# v1-mouse-has-canduino.net
KiCad netlist of a schematic drawn in EAGLE
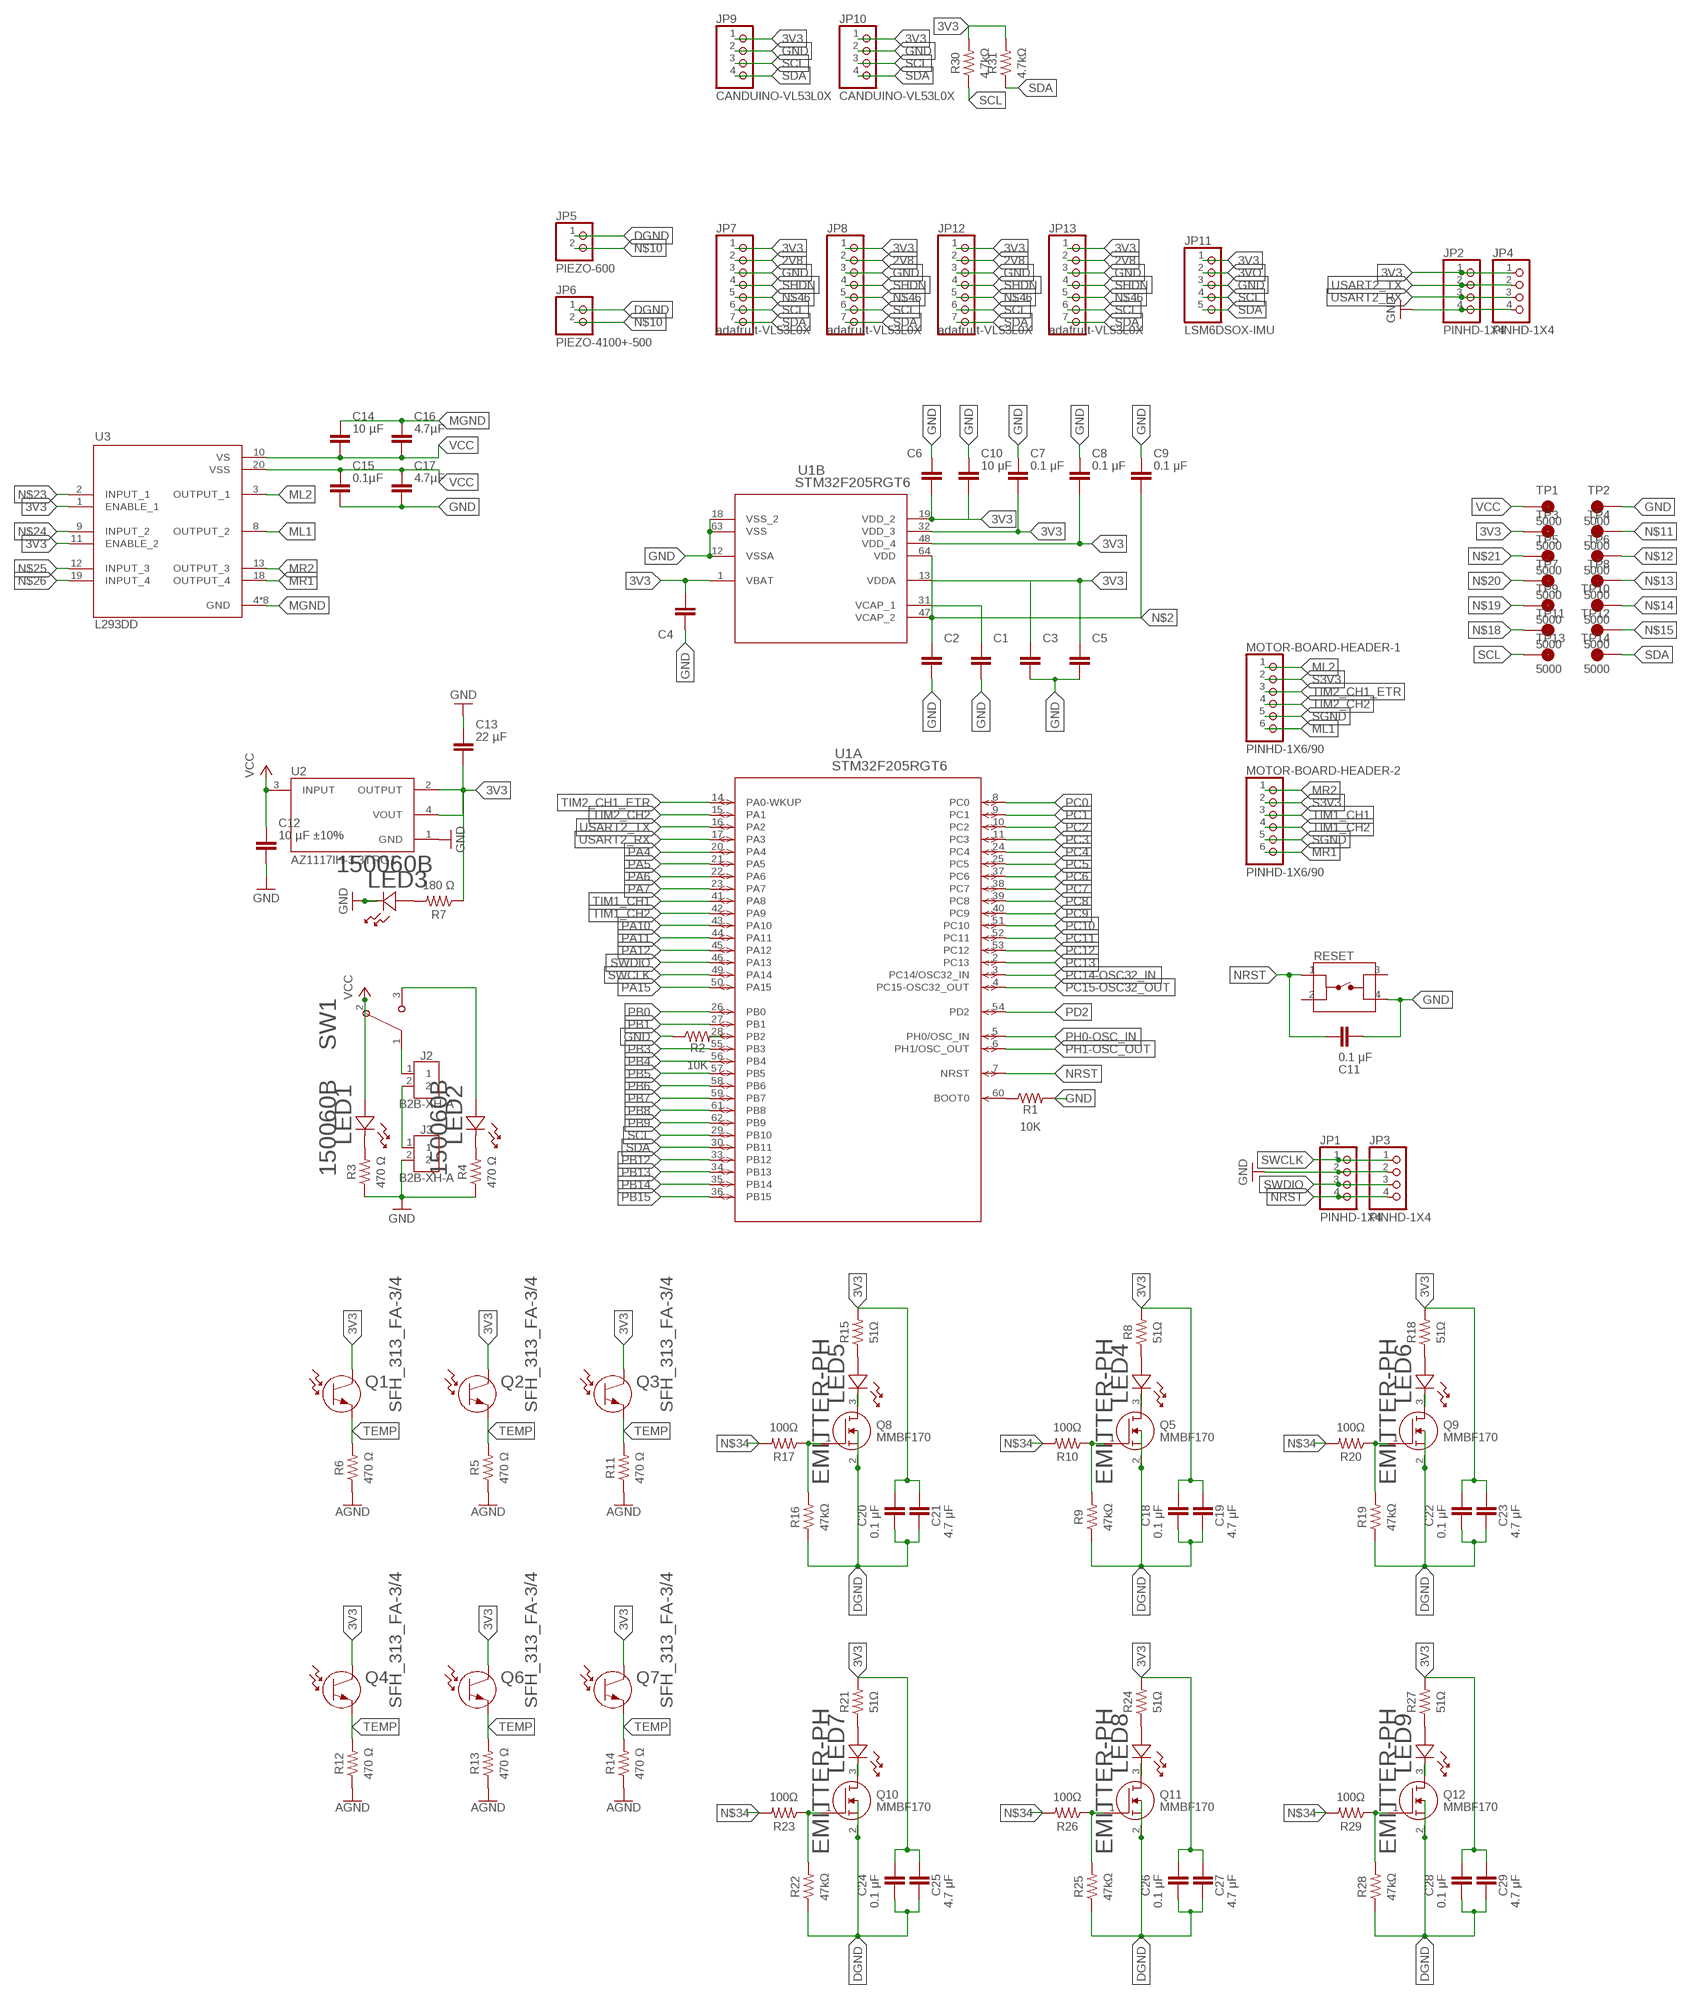
[diagram p0: schematic, sheet 1]

(export (version "E")
  (design (tool "Eeschema 10.0.6"))
  (components
    (comp (ref "C1")
      (value "2.2 μF")
      (footprint "eagle-import:CAPC1608X85")
      (libsource (lib "eagle-import") (part "CCHIP-0603(1608-METRIC)_"))
    )
    (comp (ref "C2")
      (value "2.2 μF")
      (footprint "eagle-import:CAPC1608X85")
      (libsource (lib "eagle-import") (part "CCHIP-0603(1608-METRIC)_"))
    )
    (comp (ref "C3")
      (value "0.1 μF")
      (footprint "eagle-import:CAPC1608X85")
      (libsource (lib "eagle-import") (part "CCHIP-0603(1608-METRIC)_"))
    )
    (comp (ref "C4")
      (value "0.1 μF")
      (footprint "eagle-import:CAPC1608X85")
      (libsource (lib "eagle-import") (part "CCHIP-0603(1608-METRIC)_"))
    )
    (comp (ref "C5")
      (value "1 μF")
      (footprint "eagle-import:CAPC1608X85")
      (libsource (lib "eagle-import") (part "CCHIP-0603(1608-METRIC)_"))
    )
    (comp (ref "C6")
      (value "0.1 μF")
      (footprint "eagle-import:CAPC1608X85")
      (libsource (lib "eagle-import") (part "CCHIP-0603(1608-METRIC)_"))
    )
    (comp (ref "C7")
      (value "0.1 μF")
      (footprint "eagle-import:CAPC1608X85")
      (libsource (lib "eagle-import") (part "Capacitor2_CCHIP-0603(1608-METRIC)_"))
    )
    (comp (ref "C8")
      (value "0.1 μF")
      (footprint "eagle-import:CAPC1608X85")
      (libsource (lib "eagle-import") (part "Capacitor2_CCHIP-0603(1608-METRIC)_"))
    )
    (comp (ref "C9")
      (value "0.1 μF")
      (footprint "eagle-import:CAPC1608X85")
      (libsource (lib "eagle-import") (part "Capacitor2_CCHIP-0603(1608-METRIC)_"))
    )
    (comp (ref "C10")
      (value "10 μF")
      (footprint "eagle-import:CAPC1608X85")
      (libsource (lib "eagle-import") (part "Capacitor2_CCHIP-0603(1608-METRIC)_"))
    )
    (comp (ref "C11")
      (value "0.1 μF")
      (footprint "eagle-import:CAPC1608X85")
      (libsource (lib "eagle-import") (part "Capacitor2_CCHIP-0603(1608-METRIC)_"))
    )
    (comp (ref "C12")
      (value "10 µF ±10%")
      (footprint "eagle-import:CAPC1608X85")
      (libsource (lib "eagle-import") (part "CCHIP-0603(1608-METRIC)_"))
    )
    (comp (ref "C13")
      (value "22 µF")
      (footprint "eagle-import:CAPC1608X85")
      (libsource (lib "eagle-import") (part "CCHIP-0603(1608-METRIC)_"))
    )
    (comp (ref "C14")
      (value "10 µF")
      (footprint "eagle-import:CAPC1608X85")
      (libsource (lib "eagle-import") (part "CCHIP-0603(1608-METRIC)_"))
    )
    (comp (ref "C15")
      (value "0.1µF")
      (footprint "eagle-import:CAPC1608X85")
      (libsource (lib "eagle-import") (part "CCHIP-0603(1608-METRIC)_"))
    )
    (comp (ref "C16")
      (value "4.7µF")
      (footprint "eagle-import:CAPC1608X85")
      (libsource (lib "eagle-import") (part "CCHIP-0603(1608-METRIC)_"))
    )
    (comp (ref "C17")
      (value "4.7µF")
      (footprint "eagle-import:CAPC1608X85")
      (libsource (lib "eagle-import") (part "CCHIP-0603(1608-METRIC)_"))
    )
    (comp (ref "C18")
      (value "0.1 μF")
      (footprint "eagle-import:CAPC1608X85")
      (libsource (lib "eagle-import") (part "Capacitor2_CCHIP-0603(1608-METRIC)_"))
    )
    (comp (ref "C19")
      (value "4.7 μF")
      (footprint "eagle-import:CAPC1608X85")
      (libsource (lib "eagle-import") (part "Capacitor2_CCHIP-0603(1608-METRIC)_"))
    )
    (comp (ref "C20")
      (value "0.1 μF")
      (footprint "eagle-import:CAPC1608X85")
      (libsource (lib "eagle-import") (part "Capacitor2_CCHIP-0603(1608-METRIC)_"))
    )
    (comp (ref "C21")
      (value "4.7 μF")
      (footprint "eagle-import:CAPC1608X85")
      (libsource (lib "eagle-import") (part "Capacitor2_CCHIP-0603(1608-METRIC)_"))
    )
    (comp (ref "C22")
      (value "0.1 μF")
      (footprint "eagle-import:CAPC1608X85")
      (libsource (lib "eagle-import") (part "Capacitor2_CCHIP-0603(1608-METRIC)_"))
    )
    (comp (ref "C23")
      (value "4.7 μF")
      (footprint "eagle-import:CAPC1608X85")
      (libsource (lib "eagle-import") (part "Capacitor2_CCHIP-0603(1608-METRIC)_"))
    )
    (comp (ref "C24")
      (value "0.1 μF")
      (footprint "eagle-import:CAPC1608X85")
      (libsource (lib "eagle-import") (part "Capacitor2_CCHIP-0603(1608-METRIC)_"))
    )
    (comp (ref "C25")
      (value "4.7 μF")
      (footprint "eagle-import:CAPC1608X85")
      (libsource (lib "eagle-import") (part "Capacitor2_CCHIP-0603(1608-METRIC)_"))
    )
    (comp (ref "C26")
      (value "0.1 μF")
      (footprint "eagle-import:CAPC1608X85")
      (libsource (lib "eagle-import") (part "Capacitor2_CCHIP-0603(1608-METRIC)_"))
    )
    (comp (ref "C27")
      (value "4.7 μF")
      (footprint "eagle-import:CAPC1608X85")
      (libsource (lib "eagle-import") (part "Capacitor2_CCHIP-0603(1608-METRIC)_"))
    )
    (comp (ref "C28")
      (value "0.1 μF")
      (footprint "eagle-import:CAPC1608X85")
      (libsource (lib "eagle-import") (part "Capacitor2_CCHIP-0603(1608-METRIC)_"))
    )
    (comp (ref "C29")
      (value "4.7 μF")
      (footprint "eagle-import:CAPC1608X85")
      (libsource (lib "eagle-import") (part "Capacitor2_CCHIP-0603(1608-METRIC)_"))
    )
    (comp (ref "J2")
      (value "B2B-XH-A")
      (footprint "eagle-import:B2B-XH-A")
      (fields
        (field (name "MANUFACTURER") "JST Sales America Inc. ")
        (field (name "MPN") "B2B-XH-A(LF)(SN) ")
      )
      (libsource (lib "eagle-import") (part "B2B-XH-A"))
    )
    (comp (ref "J3")
      (value "B2B-XH-A")
      (footprint "eagle-import:B2B-XH-A")
      (fields
        (field (name "MANUFACTURER") "JST Sales America Inc. ")
        (field (name "MPN") "B2B-XH-A(LF)(SN) ")
      )
      (libsource (lib "eagle-import") (part "B2B-XH-A"))
    )
    (comp (ref "JP1")
      (value "PINHD-1X4")
      (footprint "eagle-import:1X04")
      (fields (field (name "MANUFACTURER") "Generic"))
      (libsource (lib "eagle-import") (part "PINHD-1X4"))
    )
    (comp (ref "JP2")
      (value "PINHD-1X4")
      (footprint "eagle-import:1X04")
      (fields (field (name "MANUFACTURER") "Generic"))
      (libsource (lib "eagle-import") (part "PINHD-1X4"))
    )
    (comp (ref "JP3")
      (value "PINHD-1X4")
      (footprint "eagle-import:1X04")
      (fields (field (name "MANUFACTURER") "Generic"))
      (libsource (lib "eagle-import") (part "PINHD-1X4"))
    )
    (comp (ref "JP4")
      (value "PINHD-1X4")
      (footprint "eagle-import:1X04")
      (fields (field (name "MANUFACTURER") "Generic"))
      (libsource (lib "eagle-import") (part "PINHD-1X4"))
    )
    (comp (ref "JP5")
      (value "PIEZO-600")
      (footprint "eagle-import:1X02_90")
      (fields (field (name "MANUFACTURER") "Generic"))
      (libsource (lib "eagle-import") (part "PINHD-1X2/90"))
    )
    (comp (ref "JP6")
      (value "PIEZO-4100+-500")
      (footprint "eagle-import:1X02_90")
      (fields (field (name "MANUFACTURER") "Generic"))
      (libsource (lib "eagle-import") (part "PINHD-1X2/90"))
    )
    (comp (ref "JP7")
      (value "adafruit-VL53L0X")
      (footprint "eagle-import:1X07_90")
      (fields (field (name "MANUFACTURER") "Generic"))
      (libsource (lib "eagle-import") (part "PINHD-1X7/90"))
    )
    (comp (ref "JP8")
      (value "adafruit-VL53L0X")
      (footprint "eagle-import:1X07_90")
      (fields (field (name "MANUFACTURER") "Generic"))
      (libsource (lib "eagle-import") (part "PINHD-1X7/90"))
    )
    (comp (ref "JP9")
      (value "CANDUINO-VL53L0X")
      (footprint "eagle-import:1X04_90")
      (fields (field (name "MANUFACTURER") "Generic"))
      (libsource (lib "eagle-import") (part "PINHD-1X4/90"))
    )
    (comp (ref "JP10")
      (value "CANDUINO-VL53L0X")
      (footprint "eagle-import:1X04_90")
      (fields (field (name "MANUFACTURER") "Generic"))
      (libsource (lib "eagle-import") (part "PINHD-1X4/90"))
    )
    (comp (ref "JP11")
      (value "LSM6DSOX-IMU")
      (footprint "eagle-import:1_05X2MM")
      (fields (field (name "MANUFACTURER") "Generic"))
      (libsource (lib "eagle-import") (part "PINHD-1X55X2MM"))
    )
    (comp (ref "JP12")
      (value "adafruit-VL53L0X")
      (footprint "eagle-import:1X07_90")
      (fields (field (name "MANUFACTURER") "Generic"))
      (libsource (lib "eagle-import") (part "PINHD-1X7/90"))
    )
    (comp (ref "JP13")
      (value "adafruit-VL53L0X")
      (footprint "eagle-import:1X07_90")
      (fields (field (name "MANUFACTURER") "Generic"))
      (libsource (lib "eagle-import") (part "PINHD-1X7/90"))
    )
    (comp (ref "LED1")
      (value "150060B")
      (footprint "eagle-import:LED_150060B_WRE-L")
      (fields
        (field (name "MANUFACTURER_PART_NUMBER") "150060VS55040")
        (field (name "COPYRIGHT") "Copyright (C) 2024 Ultra Librarian. All rights reserved.")
      )
      (libsource (lib "eagle-import") (part "150060VS55040LED_150060B_WRE-L"))
    )
    (comp (ref "LED2")
      (value "150060B")
      (footprint "eagle-import:LED_150060B_WRE-L")
      (fields
        (field (name "MANUFACTURER_PART_NUMBER") "150060VS55040")
        (field (name "COPYRIGHT") "Copyright (C) 2024 Ultra Librarian. All rights reserved.")
      )
      (libsource (lib "eagle-import") (part "150060VS55040LED_150060B_WRE-L"))
    )
    (comp (ref "LED3")
      (value "150060B")
      (footprint "eagle-import:LED_150060B_WRE-L")
      (fields
        (field (name "MANUFACTURER_PART_NUMBER") "150060VS55040")
        (field (name "COPYRIGHT") "Copyright (C) 2024 Ultra Librarian. All rights reserved.")
      )
      (libsource (lib "eagle-import") (part "150060VS55040LED_150060B_WRE-L"))
    )
    (comp (ref "LED4")
      (value "EMITTER-PH")
      (footprint "eagle-import:LED_B1911PG--20D000514U1930_01")
      (fields
        (field (name "MANUFACTURER_PART_NUMBER") "B1911PG--20D000514U1930")
        (field (name "COPYRIGHT") "Copyright (C) 2024 Ultra Librarian. All rights reserved.")
      )
      (libsource (lib "eagle-import") (part "B1911PG--20D000514U1930LED_B1911PG--20D000514U1930_01"))
    )
    (comp (ref "LED5")
      (value "EMITTER-PH")
      (footprint "eagle-import:LED_B1911PG--20D000514U1930_01")
      (fields
        (field (name "MANUFACTURER_PART_NUMBER") "B1911PG--20D000514U1930")
        (field (name "COPYRIGHT") "Copyright (C) 2024 Ultra Librarian. All rights reserved.")
      )
      (libsource (lib "eagle-import") (part "B1911PG--20D000514U1930LED_B1911PG--20D000514U1930_01"))
    )
    (comp (ref "LED6")
      (value "EMITTER-PH")
      (footprint "eagle-import:LED_B1911PG--20D000514U1930_01")
      (fields
        (field (name "MANUFACTURER_PART_NUMBER") "B1911PG--20D000514U1930")
        (field (name "COPYRIGHT") "Copyright (C) 2024 Ultra Librarian. All rights reserved.")
      )
      (libsource (lib "eagle-import") (part "B1911PG--20D000514U1930LED_B1911PG--20D000514U1930_01"))
    )
    (comp (ref "LED7")
      (value "EMITTER-PH")
      (footprint "eagle-import:LED_B1911PG--20D000514U1930_01")
      (fields
        (field (name "MANUFACTURER_PART_NUMBER") "B1911PG--20D000514U1930")
        (field (name "COPYRIGHT") "Copyright (C) 2024 Ultra Librarian. All rights reserved.")
      )
      (libsource (lib "eagle-import") (part "B1911PG--20D000514U1930LED_B1911PG--20D000514U1930_01"))
    )
    (comp (ref "LED8")
      (value "EMITTER-PH")
      (footprint "eagle-import:LED_B1911PG--20D000514U1930_01")
      (fields
        (field (name "MANUFACTURER_PART_NUMBER") "B1911PG--20D000514U1930")
        (field (name "COPYRIGHT") "Copyright (C) 2024 Ultra Librarian. All rights reserved.")
      )
      (libsource (lib "eagle-import") (part "B1911PG--20D000514U1930LED_B1911PG--20D000514U1930_01"))
    )
    (comp (ref "LED9")
      (value "EMITTER-PH")
      (footprint "eagle-import:LED_B1911PG--20D000514U1930_01")
      (fields
        (field (name "MANUFACTURER_PART_NUMBER") "B1911PG--20D000514U1930")
        (field (name "COPYRIGHT") "Copyright (C) 2024 Ultra Librarian. All rights reserved.")
      )
      (libsource (lib "eagle-import") (part "B1911PG--20D000514U1930LED_B1911PG--20D000514U1930_01"))
    )
    (comp (ref "MOTOR-BOARD-HEADER-1")
      (value "PINHD-1X6/90")
      (footprint "eagle-import:1X06_90")
      (fields (field (name "MANUFACTURER") "Generic"))
      (libsource (lib "eagle-import") (part "PINHD-1X6/90"))
    )
    (comp (ref "MOTOR-BOARD-HEADER-2")
      (value "PINHD-1X6/90")
      (footprint "eagle-import:1X06_90")
      (fields (field (name "MANUFACTURER") "Generic"))
      (libsource (lib "eagle-import") (part "PINHD-1X6/90"))
    )
    (comp (ref "Q1")
      (value "SFH_313_FA-3/4")
      (footprint "eagle-import:SFH_313_FA-3_4_OSR")
      (fields
        (field (name "MANUFACTURER_PART_NUMBER") "SFH 313 FA-3/4")
        (field (name "COPYRIGHT") "Copyright (C) 2024 Ultra Librarian. All rights reserved.")
      )
      (libsource (lib "eagle-import") (part "SFH_313_FA-3/4SFH_313_FA-3/4_OSR"))
    )
    (comp (ref "Q2")
      (value "SFH_313_FA-3/4")
      (footprint "eagle-import:SFH_313_FA-3_4_OSR")
      (fields
        (field (name "MANUFACTURER_PART_NUMBER") "SFH 313 FA-3/4")
        (field (name "COPYRIGHT") "Copyright (C) 2024 Ultra Librarian. All rights reserved.")
      )
      (libsource (lib "eagle-import") (part "SFH_313_FA-3/4SFH_313_FA-3/4_OSR"))
    )
    (comp (ref "Q3")
      (value "SFH_313_FA-3/4")
      (footprint "eagle-import:SFH_313_FA-3_4_OSR")
      (fields
        (field (name "MANUFACTURER_PART_NUMBER") "SFH 313 FA-3/4")
        (field (name "COPYRIGHT") "Copyright (C) 2024 Ultra Librarian. All rights reserved.")
      )
      (libsource (lib "eagle-import") (part "SFH_313_FA-3/4SFH_313_FA-3/4_OSR"))
    )
    (comp (ref "Q4")
      (value "SFH_313_FA-3/4")
      (footprint "eagle-import:SFH_313_FA-3_4_OSR")
      (fields
        (field (name "MANUFACTURER_PART_NUMBER") "SFH 313 FA-3/4")
        (field (name "COPYRIGHT") "Copyright (C) 2024 Ultra Librarian. All rights reserved.")
      )
      (libsource (lib "eagle-import") (part "SFH_313_FA-3/4SFH_313_FA-3/4_OSR"))
    )
    (comp (ref "Q5")
      (value "MMBF170")
      (footprint "eagle-import:SOT96P237X111-3N")
      (fields (field (name "MOUSER_PART_NUMBER") "512-MMBF170"))
      (libsource (lib "eagle-import") (part "MMBF170"))
    )
    (comp (ref "Q6")
      (value "SFH_313_FA-3/4")
      (footprint "eagle-import:SFH_313_FA-3_4_OSR")
      (fields
        (field (name "MANUFACTURER_PART_NUMBER") "SFH 313 FA-3/4")
        (field (name "COPYRIGHT") "Copyright (C) 2024 Ultra Librarian. All rights reserved.")
      )
      (libsource (lib "eagle-import") (part "SFH_313_FA-3/4SFH_313_FA-3/4_OSR"))
    )
    (comp (ref "Q7")
      (value "SFH_313_FA-3/4")
      (footprint "eagle-import:SFH_313_FA-3_4_OSR")
      (fields
        (field (name "MANUFACTURER_PART_NUMBER") "SFH 313 FA-3/4")
        (field (name "COPYRIGHT") "Copyright (C) 2024 Ultra Librarian. All rights reserved.")
      )
      (libsource (lib "eagle-import") (part "SFH_313_FA-3/4SFH_313_FA-3/4_OSR"))
    )
    (comp (ref "Q8")
      (value "MMBF170")
      (footprint "eagle-import:SOT96P237X111-3N")
      (fields (field (name "MOUSER_PART_NUMBER") "512-MMBF170"))
      (libsource (lib "eagle-import") (part "MMBF170"))
    )
    (comp (ref "Q9")
      (value "MMBF170")
      (footprint "eagle-import:SOT96P237X111-3N")
      (fields (field (name "MOUSER_PART_NUMBER") "512-MMBF170"))
      (libsource (lib "eagle-import") (part "MMBF170"))
    )
    (comp (ref "Q10")
      (value "MMBF170")
      (footprint "eagle-import:SOT96P237X111-3N")
      (fields (field (name "MOUSER_PART_NUMBER") "512-MMBF170"))
      (libsource (lib "eagle-import") (part "MMBF170"))
    )
    (comp (ref "Q11")
      (value "MMBF170")
      (footprint "eagle-import:SOT96P237X111-3N")
      (fields (field (name "MOUSER_PART_NUMBER") "512-MMBF170"))
      (libsource (lib "eagle-import") (part "MMBF170"))
    )
    (comp (ref "Q12")
      (value "MMBF170")
      (footprint "eagle-import:SOT96P237X111-3N")
      (fields (field (name "MOUSER_PART_NUMBER") "512-MMBF170"))
      (libsource (lib "eagle-import") (part "MMBF170"))
    )
    (comp (ref "R1")
      (value "10K")
      (footprint "eagle-import:RESC1608X60")
      (libsource (lib "eagle-import") (part "Resistor2_R-USCHIP-0603(1608-METRIC)_"))
    )
    (comp (ref "R2")
      (value "10K")
      (footprint "eagle-import:RESC1608X60")
      (libsource (lib "eagle-import") (part "Resistor2_R-USCHIP-0603(1608-METRIC)_"))
    )
    (comp (ref "R3")
      (value "470 Ω")
      (footprint "eagle-import:RESC1608X60")
      (libsource (lib "eagle-import") (part "R-USCHIP-0603(1608-METRIC)_"))
    )
    (comp (ref "R4")
      (value "470 Ω")
      (footprint "eagle-import:RESC1608X60")
      (libsource (lib "eagle-import") (part "R-USCHIP-0603(1608-METRIC)_"))
    )
    (comp (ref "R5")
      (value "470 Ω")
      (footprint "eagle-import:RESC1608X60")
      (libsource (lib "eagle-import") (part "R-USCHIP-0603(1608-METRIC)_"))
    )
    (comp (ref "R6")
      (value "470 Ω")
      (footprint "eagle-import:RESC1608X60")
      (libsource (lib "eagle-import") (part "R-USCHIP-0603(1608-METRIC)_"))
    )
    (comp (ref "R7")
      (value "180 Ω")
      (footprint "eagle-import:RESC1608X60")
      (libsource (lib "eagle-import") (part "R-USCHIP-0603(1608-METRIC)_"))
    )
    (comp (ref "R8")
      (value "51Ω")
      (footprint "eagle-import:RESC1608X60")
      (libsource (lib "eagle-import") (part "R-USCHIP-0603(1608-METRIC)_"))
    )
    (comp (ref "R9")
      (value "47kΩ")
      (footprint "eagle-import:RESC1608X60")
      (libsource (lib "eagle-import") (part "R-USCHIP-0603(1608-METRIC)_"))
    )
    (comp (ref "R10")
      (value "100Ω")
      (footprint "eagle-import:RESC1608X60")
      (libsource (lib "eagle-import") (part "R-USCHIP-0603(1608-METRIC)_"))
    )
    (comp (ref "R11")
      (value "470 Ω")
      (footprint "eagle-import:RESC1608X60")
      (libsource (lib "eagle-import") (part "R-USCHIP-0603(1608-METRIC)_"))
    )
    (comp (ref "R12")
      (value "470 Ω")
      (footprint "eagle-import:RESC1608X60")
      (libsource (lib "eagle-import") (part "R-USCHIP-0603(1608-METRIC)_"))
    )
    (comp (ref "R13")
      (value "470 Ω")
      (footprint "eagle-import:RESC1608X60")
      (libsource (lib "eagle-import") (part "R-USCHIP-0603(1608-METRIC)_"))
    )
    (comp (ref "R14")
      (value "470 Ω")
      (footprint "eagle-import:RESC1608X60")
      (libsource (lib "eagle-import") (part "R-USCHIP-0603(1608-METRIC)_"))
    )
    (comp (ref "R15")
      (value "51Ω")
      (footprint "eagle-import:RESC1608X60")
      (libsource (lib "eagle-import") (part "R-USCHIP-0603(1608-METRIC)_"))
    )
    (comp (ref "R16")
      (value "47kΩ")
      (footprint "eagle-import:RESC1608X60")
      (libsource (lib "eagle-import") (part "R-USCHIP-0603(1608-METRIC)_"))
    )
    (comp (ref "R17")
      (value "100Ω")
      (footprint "eagle-import:RESC1608X60")
      (libsource (lib "eagle-import") (part "R-USCHIP-0603(1608-METRIC)_"))
    )
    (comp (ref "R18")
      (value "51Ω")
      (footprint "eagle-import:RESC1608X60")
      (libsource (lib "eagle-import") (part "R-USCHIP-0603(1608-METRIC)_"))
    )
    (comp (ref "R19")
      (value "47kΩ")
      (footprint "eagle-import:RESC1608X60")
      (libsource (lib "eagle-import") (part "R-USCHIP-0603(1608-METRIC)_"))
    )
    (comp (ref "R20")
      (value "100Ω")
      (footprint "eagle-import:RESC1608X60")
      (libsource (lib "eagle-import") (part "R-USCHIP-0603(1608-METRIC)_"))
    )
    (comp (ref "R21")
      (value "51Ω")
      (footprint "eagle-import:RESC1608X60")
      (libsource (lib "eagle-import") (part "R-USCHIP-0603(1608-METRIC)_"))
    )
    (comp (ref "R22")
      (value "47kΩ")
      (footprint "eagle-import:RESC1608X60")
      (libsource (lib "eagle-import") (part "R-USCHIP-0603(1608-METRIC)_"))
    )
    (comp (ref "R23")
      (value "100Ω")
      (footprint "eagle-import:RESC1608X60")
      (libsource (lib "eagle-import") (part "R-USCHIP-0603(1608-METRIC)_"))
    )
    (comp (ref "R24")
      (value "51Ω")
      (footprint "eagle-import:RESC1608X60")
      (libsource (lib "eagle-import") (part "R-USCHIP-0603(1608-METRIC)_"))
    )
    (comp (ref "R25")
      (value "47kΩ")
      (footprint "eagle-import:RESC1608X60")
      (libsource (lib "eagle-import") (part "R-USCHIP-0603(1608-METRIC)_"))
    )
    (comp (ref "R26")
      (value "100Ω")
      (footprint "eagle-import:RESC1608X60")
      (libsource (lib "eagle-import") (part "R-USCHIP-0603(1608-METRIC)_"))
    )
    (comp (ref "R27")
      (value "51Ω")
      (footprint "eagle-import:RESC1608X60")
      (libsource (lib "eagle-import") (part "R-USCHIP-0603(1608-METRIC)_"))
    )
    (comp (ref "R28")
      (value "47kΩ")
      (footprint "eagle-import:RESC1608X60")
      (libsource (lib "eagle-import") (part "R-USCHIP-0603(1608-METRIC)_"))
    )
    (comp (ref "R29")
      (value "100Ω")
      (footprint "eagle-import:RESC1608X60")
      (libsource (lib "eagle-import") (part "R-USCHIP-0603(1608-METRIC)_"))
    )
    (comp (ref "R30")
      (value "4.7kΩ")
      (footprint "eagle-import:RESC1608X60")
      (libsource (lib "eagle-import") (part "R-USCHIP-0603(1608-METRIC)_"))
    )
    (comp (ref "R31")
      (value "4.7kΩ")
      (footprint "eagle-import:RESC1608X60")
      (libsource (lib "eagle-import") (part "R-USCHIP-0603(1608-METRIC)_"))
    )
    (comp (ref "RESET")
      (value "FSM4JSMA")
      (footprint "eagle-import:TE_FSM4JSMA")
      (fields
        (field (name "COMMENT") "4-1437565-1")
        (field (name "DIGI-KEY_PART_NUMBER") "450-1759-2-ND")
        (field (name "MF") "TE Connectivity")
      )
      (libsource (lib "eagle-import") (part "FSM4JSMA"))
    )
    (comp (ref "SW1")
      (value "EG1218SW_1218_EWI")
      (footprint "eagle-import:SW_1218_EWI")
      (fields
        (field (name "MANUFACTURER_PART_NUMBER") "EG1218")
        (field (name "COPYRIGHT") "Copyright (C) 2024 Ultra Librarian. All rights reserved.")
      )
      (libsource (lib "eagle-import") (part "EG1218SW_1218_EWI"))
    )
    (comp (ref "TP1")
      (value "5000")
      (footprint "eagle-import:KEYSTONE_5000")
      (fields (field (name "MF") "Keystone Electronics"))
      (libsource (lib "eagle-import") (part "5000"))
    )
    (comp (ref "TP2")
      (value "5000")
      (footprint "eagle-import:KEYSTONE_5000")
      (fields (field (name "MF") "Keystone Electronics"))
      (libsource (lib "eagle-import") (part "5000"))
    )
    (comp (ref "TP3")
      (value "5000")
      (footprint "eagle-import:KEYSTONE_5000")
      (fields (field (name "MF") "Keystone Electronics"))
      (libsource (lib "eagle-import") (part "5000"))
    )
    (comp (ref "TP4")
      (value "5000")
      (footprint "eagle-import:KEYSTONE_5000")
      (fields (field (name "MF") "Keystone Electronics"))
      (libsource (lib "eagle-import") (part "5000"))
    )
    (comp (ref "TP5")
      (value "5000")
      (footprint "eagle-import:KEYSTONE_5000")
      (fields (field (name "MF") "Keystone Electronics"))
      (libsource (lib "eagle-import") (part "5000"))
    )
    (comp (ref "TP6")
      (value "5000")
      (footprint "eagle-import:KEYSTONE_5000")
      (fields (field (name "MF") "Keystone Electronics"))
      (libsource (lib "eagle-import") (part "5000"))
    )
    (comp (ref "TP7")
      (value "5000")
      (footprint "eagle-import:KEYSTONE_5000")
      (fields (field (name "MF") "Keystone Electronics"))
      (libsource (lib "eagle-import") (part "5000"))
    )
    (comp (ref "TP8")
      (value "5000")
      (footprint "eagle-import:KEYSTONE_5000")
      (fields (field (name "MF") "Keystone Electronics"))
      (libsource (lib "eagle-import") (part "5000"))
    )
    (comp (ref "TP9")
      (value "5000")
      (footprint "eagle-import:KEYSTONE_5000")
      (fields (field (name "MF") "Keystone Electronics"))
      (libsource (lib "eagle-import") (part "5000"))
    )
    (comp (ref "TP10")
      (value "5000")
      (footprint "eagle-import:KEYSTONE_5000")
      (fields (field (name "MF") "Keystone Electronics"))
      (libsource (lib "eagle-import") (part "5000"))
    )
    (comp (ref "TP11")
      (value "5000")
      (footprint "eagle-import:KEYSTONE_5000")
      (fields (field (name "MF") "Keystone Electronics"))
      (libsource (lib "eagle-import") (part "5000"))
    )
    (comp (ref "TP12")
      (value "5000")
      (footprint "eagle-import:KEYSTONE_5000")
      (fields (field (name "MF") "Keystone Electronics"))
      (libsource (lib "eagle-import") (part "5000"))
    )
    (comp (ref "TP13")
      (value "5000")
      (footprint "eagle-import:KEYSTONE_5000")
      (fields (field (name "MF") "Keystone Electronics"))
      (libsource (lib "eagle-import") (part "5000"))
    )
    (comp (ref "TP14")
      (value "5000")
      (footprint "eagle-import:KEYSTONE_5000")
      (fields (field (name "MF") "Keystone Electronics"))
      (libsource (lib "eagle-import") (part "5000"))
    )
    (comp (ref "U1")
      (value "STM32F205RGT6")
      (footprint "eagle-import:LQFP64-10X10MM")
      (fields (field (name "COPYRIGHT") "Copyright (C) 2021 Ultra Librarian. All rights reserved."))
      (libsource (lib "eagle-import") (part "STM32F205RGT6"))
    )
    (comp (ref "U2")
      (value "AZ1117IH-3.3TRG1")
      (footprint "eagle-import:SOT230P700X185-4N")
      (fields (field (name "MF") "Diodes Inc."))
      (libsource (lib "eagle-import") (part "AZ1117IH-3.3TRG1"))
    )
    (comp (ref "U3")
      (value "L293DD")
      (footprint "eagle-import:SOIC127P1032X265-20N")
      (fields (field (name "MANUFACTURER") "STMicroelectronics"))
      (libsource (lib "eagle-import") (part "L293DD"))
    )
  )
  (nets
    (net (code "1") (name "2V8") (class "Default")
      (node (ref "JP12") (pin "2") (pinfunction "2_2") (pintype "passive"))
      (node (ref "JP13") (pin "2") (pinfunction "2_2") (pintype "passive"))
      (node (ref "JP7") (pin "2") (pinfunction "2_2") (pintype "passive"))
      (node (ref "JP8") (pin "2") (pinfunction "2_2") (pintype "passive"))
    )
    (net (code "2") (name "3V3") (class "Default")
      (node (ref "C10") (pin "2") (pinfunction "2_2") (pintype "passive"))
      (node (ref "C13") (pin "2") (pinfunction "2_2") (pintype "passive"))
      (node (ref "C18") (pin "2") (pinfunction "2_2") (pintype "passive"))
      (node (ref "C19") (pin "2") (pinfunction "2_2") (pintype "passive"))
      (node (ref "C20") (pin "2") (pinfunction "2_2") (pintype "passive"))
      (node (ref "C21") (pin "2") (pinfunction "2_2") (pintype "passive"))
      (node (ref "C22") (pin "2") (pinfunction "2_2") (pintype "passive"))
      (node (ref "C23") (pin "2") (pinfunction "2_2") (pintype "passive"))
      (node (ref "C24") (pin "2") (pinfunction "2_2") (pintype "passive"))
      (node (ref "C25") (pin "2") (pinfunction "2_2") (pintype "passive"))
      (node (ref "C26") (pin "2") (pinfunction "2_2") (pintype "passive"))
      (node (ref "C27") (pin "2") (pinfunction "2_2") (pintype "passive"))
      (node (ref "C28") (pin "2") (pinfunction "2_2") (pintype "passive"))
      (node (ref "C29") (pin "2") (pinfunction "2_2") (pintype "passive"))
      (node (ref "C3") (pin "1") (pinfunction "1_1") (pintype "passive"))
      (node (ref "C4") (pin "2") (pinfunction "2_2") (pintype "passive"))
      (node (ref "C5") (pin "1") (pinfunction "1_1") (pintype "passive"))
      (node (ref "C6") (pin "2") (pinfunction "2_2") (pintype "passive"))
      (node (ref "C7") (pin "2") (pinfunction "2_2") (pintype "passive"))
      (node (ref "C8") (pin "2") (pinfunction "2_2") (pintype "passive"))
      (node (ref "JP10") (pin "1") (pinfunction "1_1") (pintype "passive"))
      (node (ref "JP11") (pin "1") (pinfunction "1_1") (pintype "passive"))
      (node (ref "JP12") (pin "1") (pinfunction "1_1") (pintype "passive"))
      (node (ref "JP13") (pin "1") (pinfunction "1_1") (pintype "passive"))
      (node (ref "JP2") (pin "1") (pinfunction "1_1") (pintype "passive"))
      (node (ref "JP4") (pin "1") (pinfunction "1_1") (pintype "passive"))
      (node (ref "JP7") (pin "1") (pinfunction "1_1") (pintype "passive"))
      (node (ref "JP8") (pin "1") (pinfunction "1_1") (pintype "passive"))
      (node (ref "JP9") (pin "1") (pinfunction "1_1") (pintype "passive"))
      (node (ref "Q1") (pin "2") (pinfunction "2_2") (pintype "passive"))
      (node (ref "Q2") (pin "2") (pinfunction "2_2") (pintype "passive"))
      (node (ref "Q3") (pin "2") (pinfunction "2_2") (pintype "passive"))
      (node (ref "Q4") (pin "2") (pinfunction "2_2") (pintype "passive"))
      (node (ref "Q6") (pin "2") (pinfunction "2_2") (pintype "passive"))
      (node (ref "Q7") (pin "2") (pinfunction "2_2") (pintype "passive"))
      (node (ref "R15") (pin "2") (pinfunction "2_2") (pintype "passive"))
      (node (ref "R18") (pin "2") (pinfunction "2_2") (pintype "passive"))
      (node (ref "R21") (pin "2") (pinfunction "2_2") (pintype "passive"))
      (node (ref "R24") (pin "2") (pinfunction "2_2") (pintype "passive"))
      (node (ref "R27") (pin "2") (pinfunction "2_2") (pintype "passive"))
      (node (ref "R30") (pin "2") (pinfunction "2_2") (pintype "passive"))
      (node (ref "R31") (pin "2") (pinfunction "2_2") (pintype "passive"))
      (node (ref "R7") (pin "1") (pinfunction "1_1") (pintype "passive"))
      (node (ref "R8") (pin "2") (pinfunction "2_2") (pintype "passive"))
      (node (ref "TP3") (pin "TP") (pinfunction "TP_TP") (pintype "passive"))
      (node (ref "U1") (pin "1") (pinfunction "VBAT_1") (pintype "power_in"))
      (node (ref "U1") (pin "13") (pinfunction "VDDA_13") (pintype "power_in"))
      (node (ref "U1") (pin "19") (pinfunction "VDD_2_19") (pintype "power_in"))
      (node (ref "U1") (pin "32") (pinfunction "VDD_3_32") (pintype "power_in"))
      (node (ref "U1") (pin "48") (pinfunction "VDD_4_48") (pintype "power_in"))
      (node (ref "U2") (pin "2") (pinfunction "OUTPUT_2") (pintype "output"))
      (node (ref "U2") (pin "4") (pinfunction "VOUT_4") (pintype "output"))
      (node (ref "U3") (pin "1") (pinfunction "ENABLE_1_1") (pintype "input"))
      (node (ref "U3") (pin "11") (pinfunction "ENABLE_2_11") (pintype "input"))
    )
    (net (code "3") (name "3VO") (class "Default")
      (node (ref "JP11") (pin "2") (pinfunction "2_2") (pintype "passive"))
    )
    (net (code "4") (name "AGND") (class "Default")
      (node (ref "R11") (pin "1") (pinfunction "1_1") (pintype "passive"))
      (node (ref "R12") (pin "1") (pinfunction "1_1") (pintype "passive"))
      (node (ref "R13") (pin "1") (pinfunction "1_1") (pintype "passive"))
      (node (ref "R14") (pin "1") (pinfunction "1_1") (pintype "passive"))
      (node (ref "R5") (pin "1") (pinfunction "1_1") (pintype "passive"))
      (node (ref "R6") (pin "1") (pinfunction "1_1") (pintype "passive"))
    )
    (net (code "5") (name "DGND") (class "Default")
      (node (ref "C18") (pin "1") (pinfunction "1_1") (pintype "passive"))
      (node (ref "C19") (pin "1") (pinfunction "1_1") (pintype "passive"))
      (node (ref "C20") (pin "1") (pinfunction "1_1") (pintype "passive"))
      (node (ref "C21") (pin "1") (pinfunction "1_1") (pintype "passive"))
      (node (ref "C22") (pin "1") (pinfunction "1_1") (pintype "passive"))
      (node (ref "C23") (pin "1") (pinfunction "1_1") (pintype "passive"))
      (node (ref "C24") (pin "1") (pinfunction "1_1") (pintype "passive"))
      (node (ref "C25") (pin "1") (pinfunction "1_1") (pintype "passive"))
      (node (ref "C26") (pin "1") (pinfunction "1_1") (pintype "passive"))
      (node (ref "C27") (pin "1") (pinfunction "1_1") (pintype "passive"))
      (node (ref "C28") (pin "1") (pinfunction "1_1") (pintype "passive"))
      (node (ref "C29") (pin "1") (pinfunction "1_1") (pintype "passive"))
      (node (ref "JP5") (pin "1") (pinfunction "1_1") (pintype "passive"))
      (node (ref "JP6") (pin "1") (pinfunction "1_1") (pintype "passive"))
      (node (ref "Q10") (pin "2") (pinfunction "S_2") (pintype "bidirectional"))
      (node (ref "Q11") (pin "2") (pinfunction "S_2") (pintype "bidirectional"))
      (node (ref "Q12") (pin "2") (pinfunction "S_2") (pintype "bidirectional"))
      (node (ref "Q5") (pin "2") (pinfunction "S_2") (pintype "bidirectional"))
      (node (ref "Q8") (pin "2") (pinfunction "S_2") (pintype "bidirectional"))
      (node (ref "Q9") (pin "2") (pinfunction "S_2") (pintype "bidirectional"))
      (node (ref "R16") (pin "1") (pinfunction "1_1") (pintype "passive"))
      (node (ref "R19") (pin "1") (pinfunction "1_1") (pintype "passive"))
      (node (ref "R22") (pin "1") (pinfunction "1_1") (pintype "passive"))
      (node (ref "R25") (pin "1") (pinfunction "1_1") (pintype "passive"))
      (node (ref "R28") (pin "1") (pinfunction "1_1") (pintype "passive"))
      (node (ref "R9") (pin "1") (pinfunction "1_1") (pintype "passive"))
    )
    (net (code "6") (name "GND") (class "Default")
      (node (ref "C1") (pin "2") (pinfunction "2_2") (pintype "passive"))
      (node (ref "C10") (pin "1") (pinfunction "1_1") (pintype "passive"))
      (node (ref "C11") (pin "1") (pinfunction "1_1") (pintype "passive"))
      (node (ref "C12") (pin "2") (pinfunction "2_2") (pintype "passive"))
      (node (ref "C13") (pin "1") (pinfunction "1_1") (pintype "passive"))
      (node (ref "C15") (pin "2") (pinfunction "2_2") (pintype "passive"))
      (node (ref "C17") (pin "2") (pinfunction "2_2") (pintype "passive"))
      (node (ref "C2") (pin "2") (pinfunction "2_2") (pintype "passive"))
      (node (ref "C3") (pin "2") (pinfunction "2_2") (pintype "passive"))
      (node (ref "C4") (pin "1") (pinfunction "1_1") (pintype "passive"))
      (node (ref "C5") (pin "2") (pinfunction "2_2") (pintype "passive"))
      (node (ref "C6") (pin "1") (pinfunction "1_1") (pintype "passive"))
      (node (ref "C7") (pin "1") (pinfunction "1_1") (pintype "passive"))
      (node (ref "C8") (pin "1") (pinfunction "1_1") (pintype "passive"))
      (node (ref "C9") (pin "1") (pinfunction "1_1") (pintype "passive"))
      (node (ref "J3") (pin "2") (pinfunction "2_2") (pintype "bidirectional"))
      (node (ref "JP1") (pin "2") (pinfunction "2_2") (pintype "passive"))
      (node (ref "JP10") (pin "2") (pinfunction "2_2") (pintype "passive"))
      (node (ref "JP11") (pin "3") (pinfunction "3_3") (pintype "passive"))
      (node (ref "JP12") (pin "3") (pinfunction "3_3") (pintype "passive"))
      (node (ref "JP13") (pin "3") (pinfunction "3_3") (pintype "passive"))
      (node (ref "JP2") (pin "4") (pinfunction "4_4") (pintype "passive"))
      (node (ref "JP3") (pin "2") (pinfunction "2_2") (pintype "passive"))
      (node (ref "JP4") (pin "4") (pinfunction "4_4") (pintype "passive"))
      (node (ref "JP7") (pin "3") (pinfunction "3_3") (pintype "passive"))
      (node (ref "JP8") (pin "3") (pinfunction "3_3") (pintype "passive"))
      (node (ref "JP9") (pin "2") (pinfunction "2_2") (pintype "passive"))
      (node (ref "LED3") (pin "1") (pinfunction "1_1") (pintype "passive"))
      (node (ref "R1") (pin "2") (pinfunction "2_2") (pintype "passive"))
      (node (ref "R2") (pin "1") (pinfunction "1_1") (pintype "passive"))
      (node (ref "R3") (pin "1") (pinfunction "1_1") (pintype "passive"))
      (node (ref "R4") (pin "1") (pinfunction "1_1") (pintype "passive"))
      (node (ref "RESET") (pin "4") (pinfunction "4_4") (pintype "passive"))
      (node (ref "TP2") (pin "TP") (pinfunction "TP_TP") (pintype "passive"))
      (node (ref "U1") (pin "12") (pinfunction "VSSA_12") (pintype "power_in"))
      (node (ref "U1") (pin "18") (pinfunction "VSS_2_18") (pintype "power_in"))
      (node (ref "U1") (pin "63") (pinfunction "VSS_63") (pintype "power_in"))
      (node (ref "U2") (pin "1") (pinfunction "GND_1") (pintype "power_in"))
    )
    (net (code "7") (name "MGND") (class "Default")
      (node (ref "C14") (pin "1") (pinfunction "1_1") (pintype "passive"))
      (node (ref "C16") (pin "1") (pinfunction "1_1") (pintype "passive"))
      (node (ref "U3") (pin "14") (pinfunction "GND_14") (pintype "power_in"))
      (node (ref "U3") (pin "15") (pinfunction "GND_15") (pintype "power_in"))
      (node (ref "U3") (pin "16") (pinfunction "GND_16") (pintype "power_in"))
      (node (ref "U3") (pin "17") (pinfunction "GND_17") (pintype "power_in"))
      (node (ref "U3") (pin "4") (pinfunction "GND_4") (pintype "power_in"))
      (node (ref "U3") (pin "5") (pinfunction "GND_5") (pintype "power_in"))
      (node (ref "U3") (pin "6") (pinfunction "GND_6") (pintype "power_in"))
      (node (ref "U3") (pin "7") (pinfunction "GND_7") (pintype "power_in"))
    )
    (net (code "8") (name "ML1") (class "Default")
      (node (ref "MOTOR-BOARD-HEADER-1") (pin "6") (pinfunction "6_6") (pintype "passive"))
      (node (ref "U3") (pin "8") (pinfunction "OUTPUT_2_8") (pintype "output"))
    )
    (net (code "9") (name "ML2") (class "Default")
      (node (ref "MOTOR-BOARD-HEADER-1") (pin "1") (pinfunction "1_1") (pintype "passive"))
      (node (ref "U3") (pin "3") (pinfunction "OUTPUT_1_3") (pintype "output"))
    )
    (net (code "10") (name "MR1") (class "Default")
      (node (ref "MOTOR-BOARD-HEADER-2") (pin "6") (pinfunction "6_6") (pintype "passive"))
      (node (ref "U3") (pin "18") (pinfunction "OUTPUT_4_18") (pintype "output"))
    )
    (net (code "11") (name "MR2") (class "Default")
      (node (ref "MOTOR-BOARD-HEADER-2") (pin "1") (pinfunction "1_1") (pintype "passive"))
      (node (ref "U3") (pin "13") (pinfunction "OUTPUT_3_13") (pintype "output"))
    )
    (net (code "12") (name "N$2") (class "Default")
      (node (ref "C2") (pin "1") (pinfunction "1_1") (pintype "passive"))
      (node (ref "C9") (pin "2") (pinfunction "2_2") (pintype "passive"))
      (node (ref "U1") (pin "47") (pinfunction "VCAP_2_47") (pintype "power_in"))
      (node (ref "U1") (pin "64") (pinfunction "VDD_64") (pintype "power_in"))
    )
    (net (code "13") (name "N$10") (class "Default")
      (node (ref "JP5") (pin "2") (pinfunction "2_2") (pintype "passive"))
      (node (ref "JP6") (pin "2") (pinfunction "2_2") (pintype "passive"))
    )
    (net (code "14") (name "N$11") (class "Default")
      (node (ref "TP4") (pin "TP") (pinfunction "TP_TP") (pintype "passive"))
    )
    (net (code "15") (name "N$12") (class "Default")
      (node (ref "TP6") (pin "TP") (pinfunction "TP_TP") (pintype "passive"))
    )
    (net (code "16") (name "N$13") (class "Default")
      (node (ref "TP8") (pin "TP") (pinfunction "TP_TP") (pintype "passive"))
    )
    (net (code "17") (name "N$14") (class "Default")
      (node (ref "TP10") (pin "TP") (pinfunction "TP_TP") (pintype "passive"))
    )
    (net (code "18") (name "N$15") (class "Default")
      (node (ref "TP12") (pin "TP") (pinfunction "TP_TP") (pintype "passive"))
    )
    (net (code "19") (name "N$18") (class "Default")
      (node (ref "TP11") (pin "TP") (pinfunction "TP_TP") (pintype "passive"))
    )
    (net (code "20") (name "N$19") (class "Default")
      (node (ref "TP9") (pin "TP") (pinfunction "TP_TP") (pintype "passive"))
    )
    (net (code "21") (name "N$20") (class "Default")
      (node (ref "TP7") (pin "TP") (pinfunction "TP_TP") (pintype "passive"))
    )
    (net (code "22") (name "N$21") (class "Default")
      (node (ref "TP5") (pin "TP") (pinfunction "TP_TP") (pintype "passive"))
    )
    (net (code "23") (name "N$23") (class "Default")
      (node (ref "U3") (pin "2") (pinfunction "INPUT_1_2") (pintype "input"))
    )
    (net (code "24") (name "N$24") (class "Default")
      (node (ref "U3") (pin "9") (pinfunction "INPUT_2_9") (pintype "input"))
    )
    (net (code "25") (name "N$25") (class "Default")
      (node (ref "U3") (pin "12") (pinfunction "INPUT_3_12") (pintype "input"))
    )
    (net (code "26") (name "N$26") (class "Default")
      (node (ref "U3") (pin "19") (pinfunction "INPUT_4_19") (pintype "input"))
    )
    (net (code "27") (name "N$34") (class "Default")
      (node (ref "R10") (pin "2") (pinfunction "2_2") (pintype "passive"))
      (node (ref "R17") (pin "2") (pinfunction "2_2") (pintype "passive"))
      (node (ref "R20") (pin "2") (pinfunction "2_2") (pintype "passive"))
      (node (ref "R23") (pin "2") (pinfunction "2_2") (pintype "passive"))
      (node (ref "R26") (pin "2") (pinfunction "2_2") (pintype "passive"))
      (node (ref "R29") (pin "2") (pinfunction "2_2") (pintype "passive"))
    )
    (net (code "28") (name "N$46") (class "Default")
      (node (ref "JP12") (pin "5") (pinfunction "5_5") (pintype "passive"))
      (node (ref "JP13") (pin "5") (pinfunction "5_5") (pintype "passive"))
      (node (ref "JP7") (pin "5") (pinfunction "5_5") (pintype "passive"))
      (node (ref "JP8") (pin "5") (pinfunction "5_5") (pintype "passive"))
    )
    (net (code "29") (name "NRST") (class "Default")
      (node (ref "C11") (pin "2") (pinfunction "2_2") (pintype "passive"))
      (node (ref "JP1") (pin "4") (pinfunction "4_4") (pintype "passive"))
      (node (ref "JP3") (pin "4") (pinfunction "4_4") (pintype "passive"))
      (node (ref "RESET") (pin "1") (pinfunction "1_1") (pintype "passive"))
      (node (ref "U1") (pin "7") (pinfunction "NRST_7") (pintype "bidirectional"))
    )
    (net (code "30") (name "Net-(J2-Pad1)") (class "Default")
      (node (ref "J2") (pin "1") (pinfunction "1_1") (pintype "bidirectional"))
      (node (ref "SW1") (pin "1") (pinfunction "1_1") (pintype "passive"))
    )
    (net (code "31") (name "Net-(J2-Pad2)") (class "Default")
      (node (ref "J2") (pin "2") (pinfunction "2_2") (pintype "bidirectional"))
      (node (ref "J3") (pin "1") (pinfunction "1_1") (pintype "bidirectional"))
    )
    (net (code "32") (name "Net-(LED1-Pad1)") (class "Default")
      (node (ref "LED1") (pin "1") (pinfunction "1_1") (pintype "passive"))
      (node (ref "R3") (pin "2") (pinfunction "2_2") (pintype "passive"))
    )
    (net (code "33") (name "Net-(LED2-Pad1)") (class "Default")
      (node (ref "LED2") (pin "1") (pinfunction "1_1") (pintype "passive"))
      (node (ref "R4") (pin "2") (pinfunction "2_2") (pintype "passive"))
    )
    (net (code "34") (name "Net-(LED2-Pad2)") (class "Default")
      (node (ref "LED2") (pin "2") (pinfunction "2_2") (pintype "passive"))
      (node (ref "SW1") (pin "3") (pinfunction "3_3") (pintype "passive"))
    )
    (net (code "35") (name "Net-(LED3-Pad2)") (class "Default")
      (node (ref "LED3") (pin "2") (pinfunction "2_2") (pintype "passive"))
      (node (ref "R7") (pin "2") (pinfunction "2_2") (pintype "passive"))
    )
    (net (code "36") (name "Net-(LED4-Pad2)") (class "Default")
      (node (ref "LED4") (pin "2") (pinfunction "2_2") (pintype "passive"))
      (node (ref "R8") (pin "1") (pinfunction "1_1") (pintype "passive"))
    )
    (net (code "37") (name "Net-(LED5-Pad2)") (class "Default")
      (node (ref "LED5") (pin "2") (pinfunction "2_2") (pintype "passive"))
      (node (ref "R15") (pin "1") (pinfunction "1_1") (pintype "passive"))
    )
    (net (code "38") (name "Net-(LED6-Pad2)") (class "Default")
      (node (ref "LED6") (pin "2") (pinfunction "2_2") (pintype "passive"))
      (node (ref "R18") (pin "1") (pinfunction "1_1") (pintype "passive"))
    )
    (net (code "39") (name "Net-(LED7-Pad2)") (class "Default")
      (node (ref "LED7") (pin "2") (pinfunction "2_2") (pintype "passive"))
      (node (ref "R21") (pin "1") (pinfunction "1_1") (pintype "passive"))
    )
    (net (code "40") (name "Net-(LED8-Pad2)") (class "Default")
      (node (ref "LED8") (pin "2") (pinfunction "2_2") (pintype "passive"))
      (node (ref "R24") (pin "1") (pinfunction "1_1") (pintype "passive"))
    )
    (net (code "41") (name "Net-(LED9-Pad2)") (class "Default")
      (node (ref "LED9") (pin "2") (pinfunction "2_2") (pintype "passive"))
      (node (ref "R27") (pin "1") (pinfunction "1_1") (pintype "passive"))
    )
    (net (code "42") (name "Net-(Q5-D)") (class "Default")
      (node (ref "LED4") (pin "1") (pinfunction "1_1") (pintype "passive"))
      (node (ref "Q5") (pin "3") (pinfunction "D_3") (pintype "bidirectional"))
    )
    (net (code "43") (name "Net-(Q5-G)") (class "Default")
      (node (ref "Q5") (pin "1") (pinfunction "G_1") (pintype "bidirectional"))
      (node (ref "R10") (pin "1") (pinfunction "1_1") (pintype "passive"))
      (node (ref "R9") (pin "2") (pinfunction "2_2") (pintype "passive"))
    )
    (net (code "44") (name "Net-(Q8-D)") (class "Default")
      (node (ref "LED5") (pin "1") (pinfunction "1_1") (pintype "passive"))
      (node (ref "Q8") (pin "3") (pinfunction "D_3") (pintype "bidirectional"))
    )
    (net (code "45") (name "Net-(Q8-G)") (class "Default")
      (node (ref "Q8") (pin "1") (pinfunction "G_1") (pintype "bidirectional"))
      (node (ref "R16") (pin "2") (pinfunction "2_2") (pintype "passive"))
      (node (ref "R17") (pin "1") (pinfunction "1_1") (pintype "passive"))
    )
    (net (code "46") (name "Net-(Q9-D)") (class "Default")
      (node (ref "LED6") (pin "1") (pinfunction "1_1") (pintype "passive"))
      (node (ref "Q9") (pin "3") (pinfunction "D_3") (pintype "bidirectional"))
    )
    (net (code "47") (name "Net-(Q9-G)") (class "Default")
      (node (ref "Q9") (pin "1") (pinfunction "G_1") (pintype "bidirectional"))
      (node (ref "R19") (pin "2") (pinfunction "2_2") (pintype "passive"))
      (node (ref "R20") (pin "1") (pinfunction "1_1") (pintype "passive"))
    )
    (net (code "48") (name "Net-(Q10-D)") (class "Default")
      (node (ref "LED7") (pin "1") (pinfunction "1_1") (pintype "passive"))
      (node (ref "Q10") (pin "3") (pinfunction "D_3") (pintype "bidirectional"))
    )
    (net (code "49") (name "Net-(Q10-G)") (class "Default")
      (node (ref "Q10") (pin "1") (pinfunction "G_1") (pintype "bidirectional"))
      (node (ref "R22") (pin "2") (pinfunction "2_2") (pintype "passive"))
      (node (ref "R23") (pin "1") (pinfunction "1_1") (pintype "passive"))
    )
    (net (code "50") (name "Net-(Q11-D)") (class "Default")
      (node (ref "LED8") (pin "1") (pinfunction "1_1") (pintype "passive"))
      (node (ref "Q11") (pin "3") (pinfunction "D_3") (pintype "bidirectional"))
    )
    (net (code "51") (name "Net-(Q11-G)") (class "Default")
      (node (ref "Q11") (pin "1") (pinfunction "G_1") (pintype "bidirectional"))
      (node (ref "R25") (pin "2") (pinfunction "2_2") (pintype "passive"))
      (node (ref "R26") (pin "1") (pinfunction "1_1") (pintype "passive"))
    )
    (net (code "52") (name "Net-(Q12-D)") (class "Default")
      (node (ref "LED9") (pin "1") (pinfunction "1_1") (pintype "passive"))
      (node (ref "Q12") (pin "3") (pinfunction "D_3") (pintype "bidirectional"))
    )
    (net (code "53") (name "Net-(Q12-G)") (class "Default")
      (node (ref "Q12") (pin "1") (pinfunction "G_1") (pintype "bidirectional"))
      (node (ref "R28") (pin "2") (pinfunction "2_2") (pintype "passive"))
      (node (ref "R29") (pin "1") (pinfunction "1_1") (pintype "passive"))
    )
    (net (code "54") (name "Net-(U1A-BOOT0)") (class "Default")
      (node (ref "R1") (pin "1") (pinfunction "1_1") (pintype "passive"))
      (node (ref "U1") (pin "60") (pinfunction "BOOT0_60") (pintype "input"))
    )
    (net (code "55") (name "Net-(U1A-PB2)") (class "Default")
      (node (ref "R2") (pin "2") (pinfunction "2_2") (pintype "passive"))
      (node (ref "U1") (pin "28") (pinfunction "PB2_28") (pintype "bidirectional"))
    )
    (net (code "56") (name "Net-(U1B-VCAP_1)") (class "Default")
      (node (ref "C1") (pin "1") (pinfunction "1_1") (pintype "passive"))
      (node (ref "U1") (pin "31") (pinfunction "VCAP_1_31") (pintype "power_in"))
    )
    (net (code "57") (name "PA4") (class "Default")
      (node (ref "U1") (pin "20") (pinfunction "PA4_20") (pintype "bidirectional"))
    )
    (net (code "58") (name "PA5") (class "Default")
      (node (ref "U1") (pin "21") (pinfunction "PA5_21") (pintype "bidirectional"))
    )
    (net (code "59") (name "PA6") (class "Default")
      (node (ref "U1") (pin "22") (pinfunction "PA6_22") (pintype "bidirectional"))
    )
    (net (code "60") (name "PA7") (class "Default")
      (node (ref "U1") (pin "23") (pinfunction "PA7_23") (pintype "bidirectional"))
    )
    (net (code "61") (name "PA10") (class "Default")
      (node (ref "U1") (pin "43") (pinfunction "PA10_43") (pintype "bidirectional"))
    )
    (net (code "62") (name "PA11") (class "Default")
      (node (ref "U1") (pin "44") (pinfunction "PA11_44") (pintype "bidirectional"))
    )
    (net (code "63") (name "PA12") (class "Default")
      (node (ref "U1") (pin "45") (pinfunction "PA12_45") (pintype "bidirectional"))
    )
    (net (code "64") (name "PA15") (class "Default")
      (node (ref "U1") (pin "50") (pinfunction "PA15_50") (pintype "bidirectional"))
    )
    (net (code "65") (name "PB0") (class "Default")
      (node (ref "U1") (pin "26") (pinfunction "PB0_26") (pintype "bidirectional"))
    )
    (net (code "66") (name "PB1") (class "Default")
      (node (ref "U1") (pin "27") (pinfunction "PB1_27") (pintype "bidirectional"))
    )
    (net (code "67") (name "PB3") (class "Default")
      (node (ref "U1") (pin "55") (pinfunction "PB3_55") (pintype "bidirectional"))
    )
    (net (code "68") (name "PB4") (class "Default")
      (node (ref "U1") (pin "56") (pinfunction "PB4_56") (pintype "bidirectional"))
    )
    (net (code "69") (name "PB5") (class "Default")
      (node (ref "U1") (pin "57") (pinfunction "PB5_57") (pintype "bidirectional"))
    )
    (net (code "70") (name "PB6") (class "Default")
      (node (ref "U1") (pin "58") (pinfunction "PB6_58") (pintype "bidirectional"))
    )
    (net (code "71") (name "PB7") (class "Default")
      (node (ref "U1") (pin "59") (pinfunction "PB7_59") (pintype "bidirectional"))
    )
    (net (code "72") (name "PB8") (class "Default")
      (node (ref "U1") (pin "61") (pinfunction "PB8_61") (pintype "bidirectional"))
    )
    (net (code "73") (name "PB9") (class "Default")
      (node (ref "U1") (pin "62") (pinfunction "PB9_62") (pintype "bidirectional"))
    )
    (net (code "74") (name "PB12") (class "Default")
      (node (ref "U1") (pin "33") (pinfunction "PB12_33") (pintype "bidirectional"))
    )
    (net (code "75") (name "PB13") (class "Default")
      (node (ref "U1") (pin "34") (pinfunction "PB13_34") (pintype "bidirectional"))
    )
    (net (code "76") (name "PB14") (class "Default")
      (node (ref "U1") (pin "35") (pinfunction "PB14_35") (pintype "bidirectional"))
    )
    (net (code "77") (name "PB15") (class "Default")
      (node (ref "U1") (pin "36") (pinfunction "PB15_36") (pintype "bidirectional"))
    )
    (net (code "78") (name "PC0") (class "Default")
      (node (ref "U1") (pin "8") (pinfunction "PC0_8") (pintype "bidirectional"))
    )
    (net (code "79") (name "PC1") (class "Default")
      (node (ref "U1") (pin "9") (pinfunction "PC1_9") (pintype "bidirectional"))
    )
    (net (code "80") (name "PC2") (class "Default")
      (node (ref "U1") (pin "10") (pinfunction "PC2_10") (pintype "bidirectional"))
    )
    (net (code "81") (name "PC3") (class "Default")
      (node (ref "U1") (pin "11") (pinfunction "PC3_11") (pintype "bidirectional"))
    )
    (net (code "82") (name "PC4") (class "Default")
      (node (ref "U1") (pin "24") (pinfunction "PC4_24") (pintype "bidirectional"))
    )
    (net (code "83") (name "PC5") (class "Default")
      (node (ref "U1") (pin "25") (pinfunction "PC5_25") (pintype "bidirectional"))
    )
    (net (code "84") (name "PC6") (class "Default")
      (node (ref "U1") (pin "37") (pinfunction "PC6_37") (pintype "bidirectional"))
    )
    (net (code "85") (name "PC7") (class "Default")
      (node (ref "U1") (pin "38") (pinfunction "PC7_38") (pintype "bidirectional"))
    )
    (net (code "86") (name "PC8") (class "Default")
      (node (ref "U1") (pin "39") (pinfunction "PC8_39") (pintype "bidirectional"))
    )
    (net (code "87") (name "PC9") (class "Default")
      (node (ref "U1") (pin "40") (pinfunction "PC9_40") (pintype "bidirectional"))
    )
    (net (code "88") (name "PC10") (class "Default")
      (node (ref "U1") (pin "51") (pinfunction "PC10_51") (pintype "bidirectional"))
    )
    (net (code "89") (name "PC11") (class "Default")
      (node (ref "U1") (pin "52") (pinfunction "PC11_52") (pintype "bidirectional"))
    )
    (net (code "90") (name "PC12") (class "Default")
      (node (ref "U1") (pin "53") (pinfunction "PC12_53") (pintype "bidirectional"))
    )
    (net (code "91") (name "PC13") (class "Default")
      (node (ref "U1") (pin "2") (pinfunction "PC13_2") (pintype "bidirectional"))
    )
    (net (code "92") (name "PC14-OSC32_IN") (class "Default")
      (node (ref "U1") (pin "3") (pinfunction "PC14/OSC32_IN_3") (pintype "bidirectional"))
    )
    (net (code "93") (name "PC15-OSC32_OUT") (class "Default")
      (node (ref "U1") (pin "4") (pinfunction "PC15-OSC32_OUT_4") (pintype "bidirectional"))
    )
    (net (code "94") (name "PD2") (class "Default")
      (node (ref "U1") (pin "54") (pinfunction "PD2_54") (pintype "bidirectional"))
    )
    (net (code "95") (name "PH0-OSC_IN") (class "Default")
      (node (ref "U1") (pin "5") (pinfunction "PH0/OSC_IN_5") (pintype "bidirectional"))
    )
    (net (code "96") (name "PH1-OSC_OUT") (class "Default")
      (node (ref "U1") (pin "6") (pinfunction "PH1/OSC_OUT_6") (pintype "bidirectional"))
    )
    (net (code "97") (name "S3V3") (class "Default")
      (node (ref "MOTOR-BOARD-HEADER-1") (pin "2") (pinfunction "2_2") (pintype "passive"))
      (node (ref "MOTOR-BOARD-HEADER-2") (pin "2") (pinfunction "2_2") (pintype "passive"))
    )
    (net (code "98") (name "SCL") (class "Default")
      (node (ref "JP10") (pin "3") (pinfunction "3_3") (pintype "passive"))
      (node (ref "JP11") (pin "4") (pinfunction "4_4") (pintype "passive"))
      (node (ref "JP12") (pin "6") (pinfunction "6_6") (pintype "passive"))
      (node (ref "JP13") (pin "6") (pinfunction "6_6") (pintype "passive"))
      (node (ref "JP7") (pin "6") (pinfunction "6_6") (pintype "passive"))
      (node (ref "JP8") (pin "6") (pinfunction "6_6") (pintype "passive"))
      (node (ref "JP9") (pin "3") (pinfunction "3_3") (pintype "passive"))
      (node (ref "R30") (pin "1") (pinfunction "1_1") (pintype "passive"))
      (node (ref "TP13") (pin "TP") (pinfunction "TP_TP") (pintype "passive"))
      (node (ref "U1") (pin "29") (pinfunction "PB10_29") (pintype "bidirectional"))
    )
    (net (code "99") (name "SDA") (class "Default")
      (node (ref "JP10") (pin "4") (pinfunction "4_4") (pintype "passive"))
      (node (ref "JP11") (pin "5") (pinfunction "5_5") (pintype "passive"))
      (node (ref "JP12") (pin "7") (pinfunction "7_7") (pintype "passive"))
      (node (ref "JP13") (pin "7") (pinfunction "7_7") (pintype "passive"))
      (node (ref "JP7") (pin "7") (pinfunction "7_7") (pintype "passive"))
      (node (ref "JP8") (pin "7") (pinfunction "7_7") (pintype "passive"))
      (node (ref "JP9") (pin "4") (pinfunction "4_4") (pintype "passive"))
      (node (ref "R31") (pin "1") (pinfunction "1_1") (pintype "passive"))
      (node (ref "TP14") (pin "TP") (pinfunction "TP_TP") (pintype "passive"))
      (node (ref "U1") (pin "30") (pinfunction "PB11_30") (pintype "bidirectional"))
    )
    (net (code "100") (name "SGND") (class "Default")
      (node (ref "MOTOR-BOARD-HEADER-1") (pin "5") (pinfunction "5_5") (pintype "passive"))
      (node (ref "MOTOR-BOARD-HEADER-2") (pin "5") (pinfunction "5_5") (pintype "passive"))
    )
    (net (code "101") (name "SHDN") (class "Default")
      (node (ref "JP12") (pin "4") (pinfunction "4_4") (pintype "passive"))
      (node (ref "JP13") (pin "4") (pinfunction "4_4") (pintype "passive"))
      (node (ref "JP7") (pin "4") (pinfunction "4_4") (pintype "passive"))
      (node (ref "JP8") (pin "4") (pinfunction "4_4") (pintype "passive"))
    )
    (net (code "102") (name "SWCLK") (class "Default")
      (node (ref "JP1") (pin "1") (pinfunction "1_1") (pintype "passive"))
      (node (ref "JP3") (pin "1") (pinfunction "1_1") (pintype "passive"))
      (node (ref "U1") (pin "49") (pinfunction "PA14_49") (pintype "bidirectional"))
    )
    (net (code "103") (name "SWDIO") (class "Default")
      (node (ref "JP1") (pin "3") (pinfunction "3_3") (pintype "passive"))
      (node (ref "JP3") (pin "3") (pinfunction "3_3") (pintype "passive"))
      (node (ref "U1") (pin "46") (pinfunction "PA13_46") (pintype "bidirectional"))
    )
    (net (code "104") (name "TEMP") (class "Default")
      (node (ref "Q1") (pin "1") (pinfunction "1_1") (pintype "passive"))
      (node (ref "Q2") (pin "1") (pinfunction "1_1") (pintype "passive"))
      (node (ref "Q3") (pin "1") (pinfunction "1_1") (pintype "passive"))
      (node (ref "Q4") (pin "1") (pinfunction "1_1") (pintype "passive"))
      (node (ref "Q6") (pin "1") (pinfunction "1_1") (pintype "passive"))
      (node (ref "Q7") (pin "1") (pinfunction "1_1") (pintype "passive"))
      (node (ref "R11") (pin "2") (pinfunction "2_2") (pintype "passive"))
      (node (ref "R12") (pin "2") (pinfunction "2_2") (pintype "passive"))
      (node (ref "R13") (pin "2") (pinfunction "2_2") (pintype "passive"))
      (node (ref "R14") (pin "2") (pinfunction "2_2") (pintype "passive"))
      (node (ref "R5") (pin "2") (pinfunction "2_2") (pintype "passive"))
      (node (ref "R6") (pin "2") (pinfunction "2_2") (pintype "passive"))
    )
    (net (code "105") (name "TIM1_CH1") (class "Default")
      (node (ref "MOTOR-BOARD-HEADER-2") (pin "3") (pinfunction "3_3") (pintype "passive"))
      (node (ref "U1") (pin "41") (pinfunction "PA8_41") (pintype "bidirectional"))
    )
    (net (code "106") (name "TIM1_CH2") (class "Default")
      (node (ref "MOTOR-BOARD-HEADER-2") (pin "4") (pinfunction "4_4") (pintype "passive"))
      (node (ref "U1") (pin "42") (pinfunction "PA9_42") (pintype "bidirectional"))
    )
    (net (code "107") (name "TIM2_CH1_ETR") (class "Default")
      (node (ref "MOTOR-BOARD-HEADER-1") (pin "3") (pinfunction "3_3") (pintype "passive"))
      (node (ref "U1") (pin "14") (pinfunction "PA0-WKUP_14") (pintype "bidirectional"))
    )
    (net (code "108") (name "TIM2_CH2") (class "Default")
      (node (ref "MOTOR-BOARD-HEADER-1") (pin "4") (pinfunction "4_4") (pintype "passive"))
      (node (ref "U1") (pin "15") (pinfunction "PA1_15") (pintype "bidirectional"))
    )
    (net (code "109") (name "USART2_RX") (class "Default")
      (node (ref "JP2") (pin "3") (pinfunction "3_3") (pintype "passive"))
      (node (ref "JP4") (pin "3") (pinfunction "3_3") (pintype "passive"))
      (node (ref "U1") (pin "17") (pinfunction "PA3_17") (pintype "bidirectional"))
    )
    (net (code "110") (name "USART2_TX") (class "Default")
      (node (ref "JP2") (pin "2") (pinfunction "2_2") (pintype "passive"))
      (node (ref "JP4") (pin "2") (pinfunction "2_2") (pintype "passive"))
      (node (ref "U1") (pin "16") (pinfunction "PA2_16") (pintype "bidirectional"))
    )
    (net (code "111") (name "VCC") (class "Default")
      (node (ref "C12") (pin "1") (pinfunction "1_1") (pintype "passive"))
      (node (ref "C14") (pin "2") (pinfunction "2_2") (pintype "passive"))
      (node (ref "C15") (pin "1") (pinfunction "1_1") (pintype "passive"))
      (node (ref "C16") (pin "2") (pinfunction "2_2") (pintype "passive"))
      (node (ref "C17") (pin "1") (pinfunction "1_1") (pintype "passive"))
      (node (ref "LED1") (pin "2") (pinfunction "2_2") (pintype "passive"))
      (node (ref "SW1") (pin "2") (pinfunction "2_2") (pintype "passive"))
      (node (ref "TP1") (pin "TP") (pinfunction "TP_TP") (pintype "passive"))
      (node (ref "U2") (pin "3") (pinfunction "INPUT_3") (pintype "input"))
      (node (ref "U3") (pin "10") (pinfunction "VS_10") (pintype "power_in"))
      (node (ref "U3") (pin "20") (pinfunction "VSS_20") (pintype "power_in"))
    )
    (net (code "112") (name "unconnected-(RESET-Pad2)") (class "Default")
      (node (ref "RESET") (pin "2") (pinfunction "2_2") (pintype "passive"))
    )
    (net (code "113") (name "unconnected-(RESET-Pad3)") (class "Default")
      (node (ref "RESET") (pin "3") (pinfunction "3_3") (pintype "passive"))
    )
  )
)
